# Mega2560.net
KiCad netlist of a schematic drawn in Altium Designer
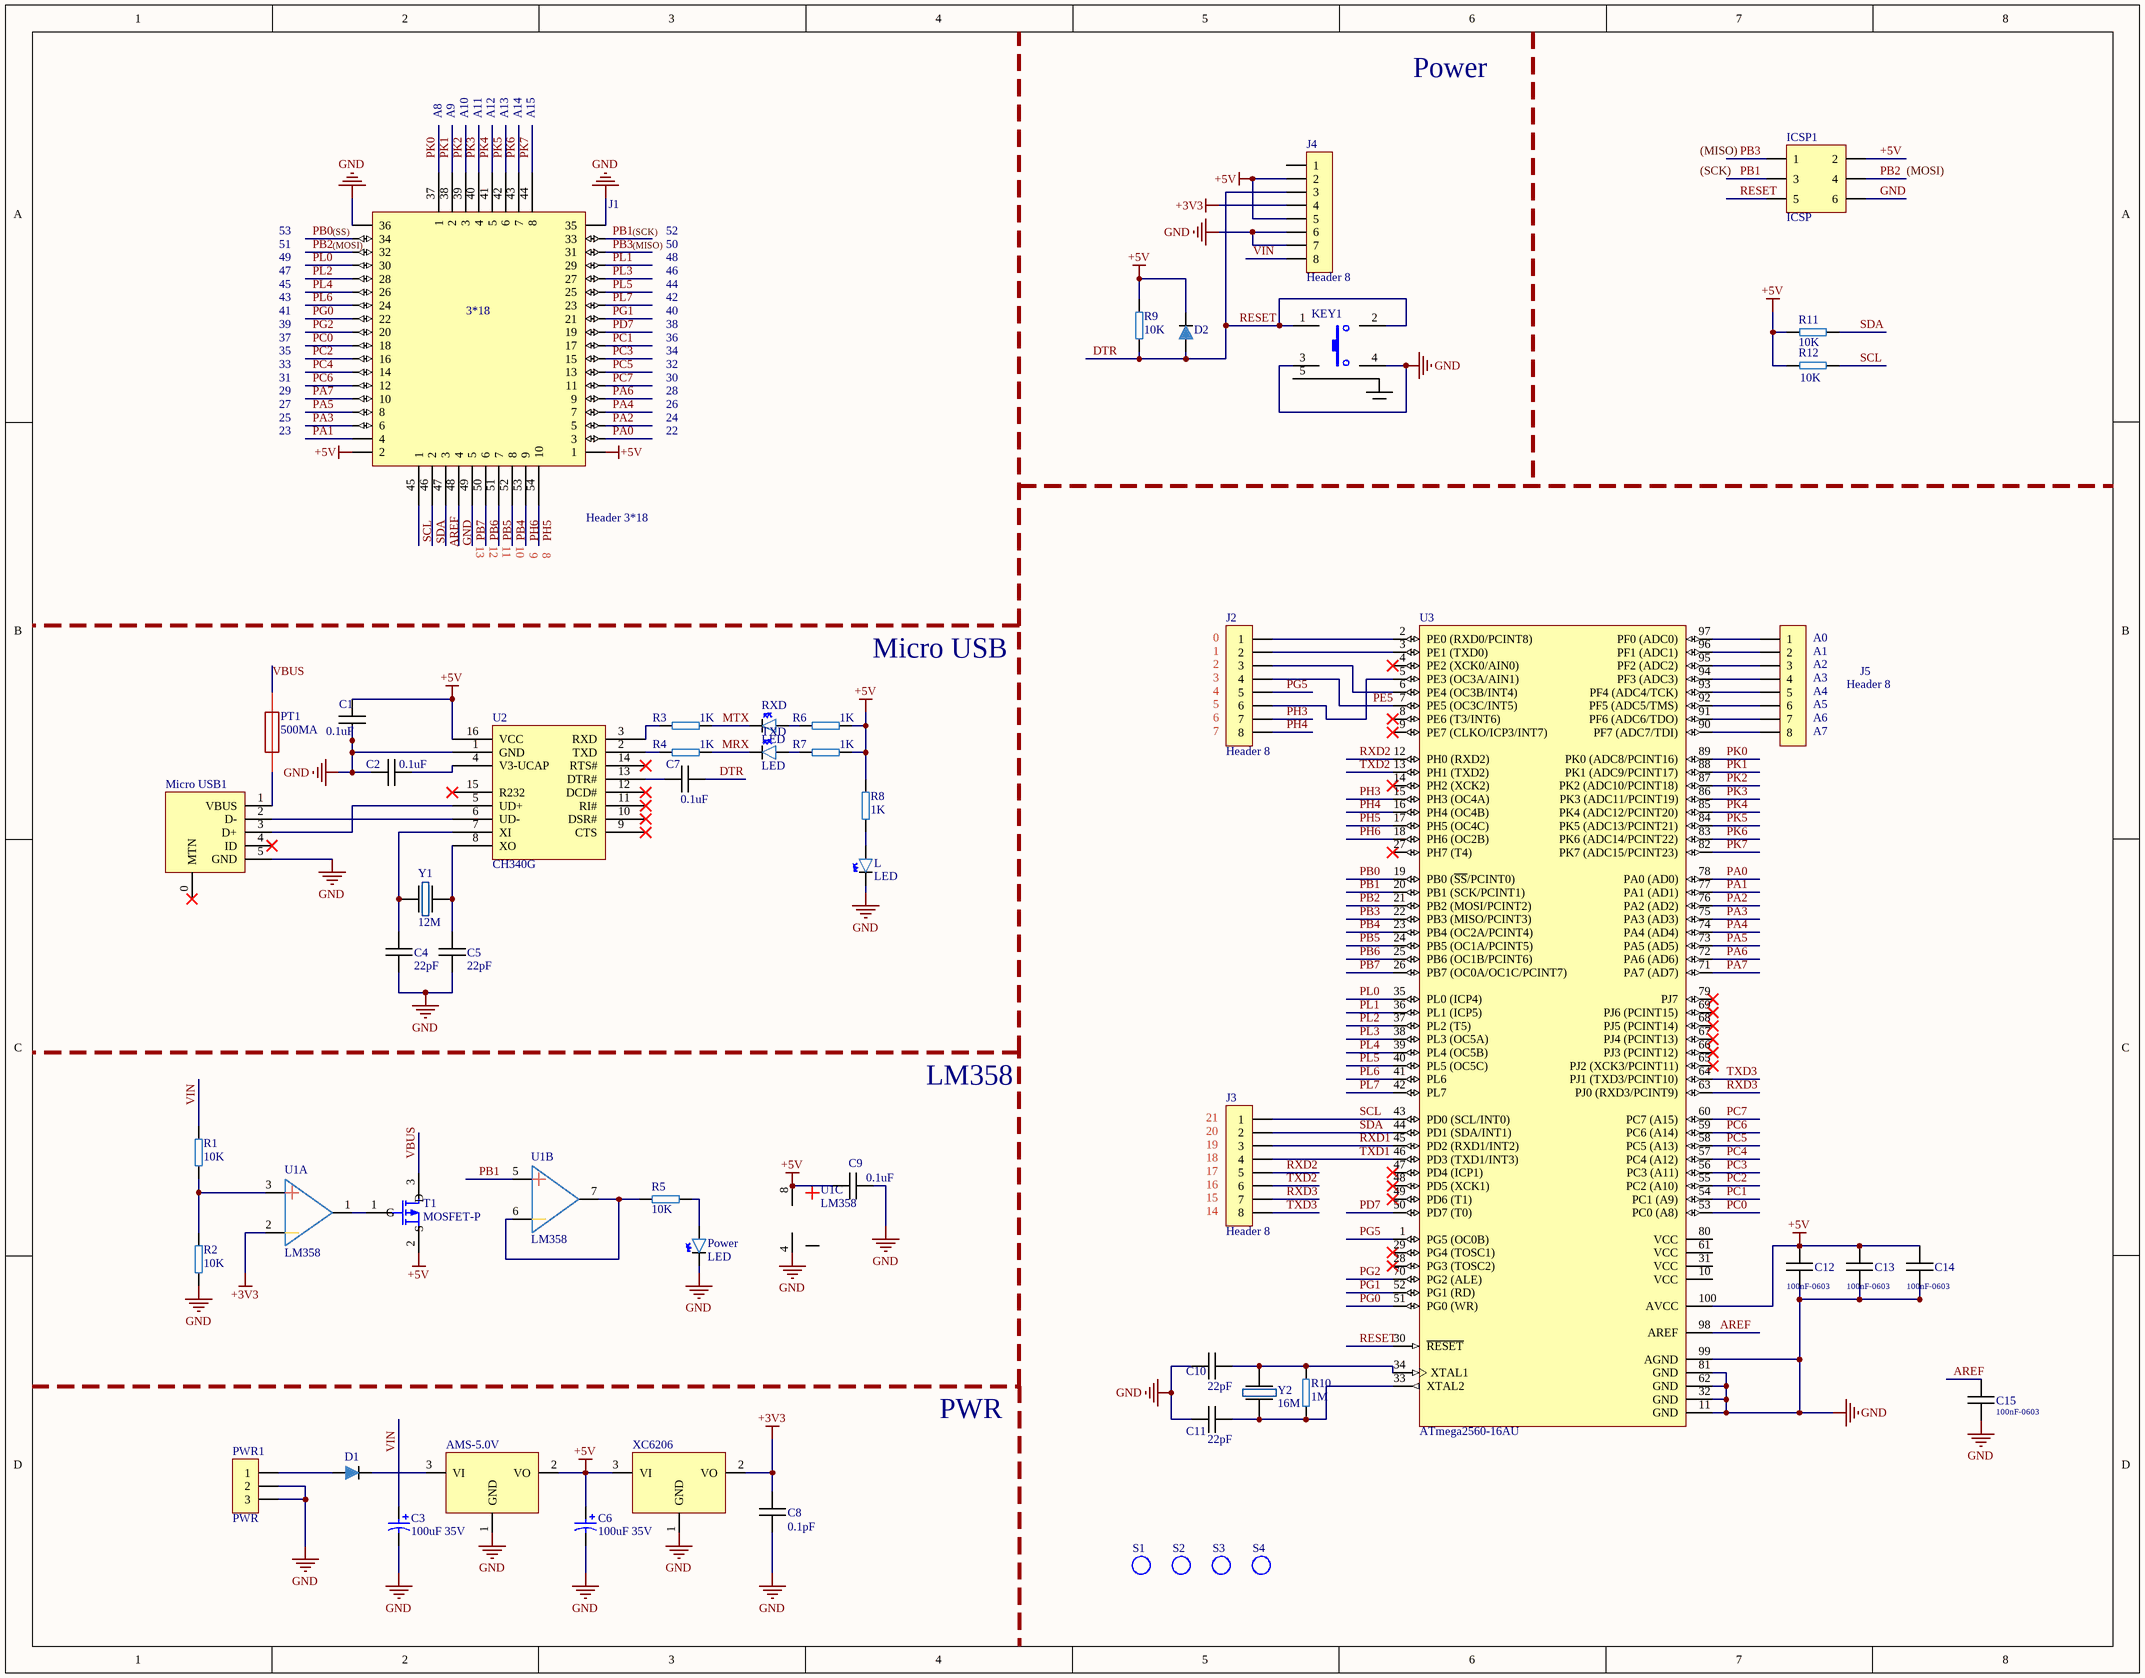
[diagram p0: Mega2560原理图.SchDoc]

(export (version "E")
  (design (tool "Eeschema 10.0.6"))
  (components
    (comp (ref "AMS-5.0V")
      (value "AMS1117-5.0")
      (footprint "AMS1117-5.0v")
      (libsource (lib "UNO原理图库") (part "AMS1117-5.0"))
    )
    (comp (ref "C1") (value "0.1uF") (footprint "0805") (libsource (lib "UNO原理图库") (part "CAP")))
    (comp (ref "C2") (value "0.1uF") (footprint "0805") (libsource (lib "UNO原理图库") (part "CAP")))
    (comp (ref "C3")
      (value "100uF 35V")
      (footprint "极性电容")
      (description "极性电容器")
      (fields (field (name "PUBLISHER") "Altium Limited"))
      (libsource (lib "UNO原理图库") (part "Cap Pol极性电容"))
    )
    (comp (ref "C4") (value "22pF") (footprint "0805") (libsource (lib "UNO原理图库") (part "CAP")))
    (comp (ref "C5") (value "22pF") (footprint "0805") (libsource (lib "UNO原理图库") (part "CAP")))
    (comp (ref "C6")
      (value "100uF 35V")
      (footprint "极性电容")
      (description "极性电容器")
      (fields (field (name "PUBLISHER") "Altium Limited"))
      (libsource (lib "UNO原理图库") (part "Cap Pol极性电容"))
    )
    (comp (ref "C7") (value "0.1uF") (footprint "0805") (libsource (lib "UNO原理图库") (part "CAP")))
    (comp (ref "C8") (value "0.1pF") (footprint "0805") (libsource (lib "UNO原理图库") (part "CAP电容")))
    (comp (ref "C9") (value "0.1uF") (footprint "0805") (libsource (lib "UNO原理图库") (part "CAP")))
    (comp (ref "C10") (value "22pF") (footprint "0805") (libsource (lib "UNO原理图库") (part "CAP")))
    (comp (ref "C11") (value "22pF") (footprint "0805") (libsource (lib "UNO原理图库") (part "CAP")))
    (comp (ref "C12")
      (value "100nF-0603")
      (footprint "0603_CAP")
      (description "0603 50V")
      (libsource (lib "Mega2560原理图库") (part "CAP-0603"))
    )
    (comp (ref "C13")
      (value "100nF-0603")
      (footprint "0603_CAP")
      (description "0603 50V")
      (libsource (lib "Mega2560原理图库") (part "CAP-0603"))
    )
    (comp (ref "C14")
      (value "100nF-0603")
      (footprint "0603_CAP")
      (description "0603 50V")
      (libsource (lib "Mega2560原理图库") (part "CAP-0603"))
    )
    (comp (ref "C15")
      (value "100nF-0603")
      (footprint "0603_CAP")
      (description "0603 50V")
      (libsource (lib "Mega2560原理图库") (part "CAP-0603"))
    )
    (comp (ref "D1") (value "二极管") (footprint "1206 正负") (libsource (lib "UNO原理图库") (part "二极管")))
    (comp (ref "D2") (value "二极管") (footprint "1206 正负") (libsource (lib "UNO原理图库") (part "二极管")))
    (comp (ref "ICSP1")
      (value "ICSP")
      (footprint "排针 2*3 PIN")
      (description "排针")
      (libsource (lib "Mega2560原理图库") (part "Header 2*3"))
    )
    (comp (ref "J1")
      (value "Header 3*18")
      (footprint "排针 3*18 PIN")
      (libsource (lib "Mega2560原理图库") (part "Header 3*18"))
    )
    (comp (ref "J2")
      (value "Header 8")
      (footprint "排针 8 PIN")
      (description "排针")
      (libsource (lib "") (part "Header 8_1"))
    )
    (comp (ref "J3")
      (value "Header 8")
      (footprint "排针 8 PIN")
      (description "排针")
      (libsource (lib "") (part "Header 8_1"))
    )
    (comp (ref "J4")
      (value "Header 8")
      (footprint "排针 8 PIN")
      (description "排针")
      (libsource (lib "Mega2560原理图库") (part "Header 8"))
    )
    (comp (ref "J5")
      (value "Header 8")
      (footprint "排针 8 PIN")
      (description "排针")
      (libsource (lib "Mega2560原理图库") (part "Header 8"))
    )
    (comp (ref "KEY1")
      (value "按键")
      (footprint "按键")
      (description "Switch")
      (fields (field (name "PUBLISHER") "Altium Limited"))
      (libsource (lib "Mega2560原理图库") (part "按键"))
    )
    (comp (ref "L") (value "LED") (footprint "0805 - LED") (libsource (lib "Mega2560原理图库") (part "LED")))
    (comp (ref "Micro USB1")
      (value "Micro USB")
      (footprint "MICRO-USB")
      (libsource (lib "UNO原理图库") (part "Micro USB"))
    )
    (comp (ref "Power") (value "LED") (footprint "0805 - LED") (libsource (lib "Mega2560原理图库") (part "LED")))
    (comp (ref "PT1")
      (value "500MA")
      (footprint "0805")
      (description "磁珠")
      (libsource (lib "UNO原理图库") (part "PT"))
    )
    (comp (ref "PWR1") (value "PWR") (footprint "DC电源") (libsource (lib "UNO原理图库") (part "PWR")))
    (comp (ref "R1") (value "10K") (footprint "0805") (libsource (lib "UNO原理图库") (part "RES")))
    (comp (ref "R2") (value "10K") (footprint "0805") (libsource (lib "UNO原理图库") (part "RES")))
    (comp (ref "R3") (value "1K") (footprint "0805") (libsource (lib "UNO原理图库") (part "RES")))
    (comp (ref "R4") (value "1K") (footprint "0805") (libsource (lib "UNO原理图库") (part "RES")))
    (comp (ref "R5") (value "10K") (footprint "0805") (libsource (lib "UNO原理图库") (part "RES")))
    (comp (ref "R6") (value "1K") (footprint "0805") (libsource (lib "UNO原理图库") (part "RES")))
    (comp (ref "R7") (value "1K") (footprint "0805") (libsource (lib "UNO原理图库") (part "RES")))
    (comp (ref "R8") (value "1K") (footprint "0805") (libsource (lib "UNO原理图库") (part "RES")))
    (comp (ref "R9") (value "10K") (footprint "0805") (libsource (lib "UNO原理图库") (part "RES")))
    (comp (ref "R10") (value "1M") (footprint "0805") (libsource (lib "UNO原理图库") (part "RES")))
    (comp (ref "R11") (value "10K") (footprint "0805") (libsource (lib "Mega2560原理图库") (part "电阻")))
    (comp (ref "R12") (value "10K") (footprint "0805") (libsource (lib "Mega2560原理图库") (part "电阻")))
    (comp (ref "RXD") (value "LED") (footprint "0805 - LED") (libsource (lib "Mega2560原理图库") (part "LED")))
    (comp (ref "S1") (value "散热孔") (footprint "散热孔") (libsource (lib "Mega2560原理图库") (part "散热孔")))
    (comp (ref "S2") (value "散热孔") (footprint "散热孔") (libsource (lib "Mega2560原理图库") (part "散热孔")))
    (comp (ref "S3") (value "散热孔") (footprint "散热孔") (libsource (lib "Mega2560原理图库") (part "散热孔")))
    (comp (ref "S4") (value "散热孔") (footprint "散热孔") (libsource (lib "Mega2560原理图库") (part "散热孔")))
    (comp (ref "T1")
      (value "MOSFET-P")
      (footprint "SI2301")
      (description "摩斯管")
      (fields (field (name "PUBLISHER") "Altium Limited"))
      (libsource (lib "Mega2560原理图库") (part "MOSFET-P(MOS)"))
    )
    (comp (ref "TXD") (value "LED") (footprint "0805 - LED") (libsource (lib "Mega2560原理图库") (part "LED")))
    (comp (ref "U1")
      (value "LM358")
      (footprint "LM358")
      (description "电源控制")
      (libsource (lib "UNO原理图库") (part "LM358"))
    )
    (comp (ref "U2") (value "CH340G") (footprint "CH340G") (libsource (lib "UNO原理图库") (part "CH340G")))
    (comp (ref "U3")
      (value "ATmega2560-16AU")
      (footprint "ATMEGA2560-AU")
      (libsource (lib "Mega2560原理图库") (part "ATmega2560-16AU"))
    )
    (comp (ref "XC6206")
      (value "XC6206P332")
      (footprint "XC6206P332-3.3v")
      (libsource (lib "UNO原理图库") (part "XC6206P332"))
    )
    (comp (ref "Y1") (value "12M") (footprint "贴片晶振") (libsource (lib "UNO原理图库") (part "CRYSTAL")))
    (comp (ref "Y2") (value "16M") (footprint "贴片晶振") (libsource (lib "UNO原理图库") (part "CRYSTAL")))
  )
  (nets
    (net (code "1") (name "+3V3") (class "Default")
      (node (ref "C8") (pin "2") (pinfunction "2_2") (pintype "passive"))
      (node (ref "J4") (pin "4") (pinfunction "4_4") (pintype "passive"))
      (node (ref "U1") (pin "2") (pinfunction "2_2") (pintype "passive"))
      (node (ref "XC6206") (pin "2") (pinfunction "VO_2") (pintype "passive"))
    )
    (net (code "2") (name "+5V") (class "Default")
      (node (ref "AMS-5.0V") (pin "2") (pinfunction "VO_2") (pintype "passive"))
      (node (ref "C1") (pin "2") (pinfunction "2_2") (pintype "passive"))
      (node (ref "C12") (pin "2") (pinfunction "2_2") (pintype "passive"))
      (node (ref "C13") (pin "2") (pinfunction "2_2") (pintype "passive"))
      (node (ref "C14") (pin "2") (pinfunction "2_2") (pintype "passive"))
      (node (ref "C6") (pin "1") (pinfunction "1_1") (pintype "passive"))
      (node (ref "C9") (pin "1") (pinfunction "1_1") (pintype "passive"))
      (node (ref "D2") (pin "2") (pinfunction "2_2") (pintype "passive"))
      (node (ref "ICSP1") (pin "2") (pinfunction "2_2") (pintype "passive"))
      (node (ref "J1") (pin "1") (pinfunction "1_1") (pintype "power_in"))
      (node (ref "J1") (pin "2") (pinfunction "2_2") (pintype "power_in"))
      (node (ref "J4") (pin "2") (pinfunction "2_2") (pintype "passive"))
      (node (ref "J4") (pin "5") (pinfunction "5_5") (pintype "passive"))
      (node (ref "R11") (pin "2") (pinfunction "2_2") (pintype "passive"))
      (node (ref "R12") (pin "2") (pinfunction "2_2") (pintype "passive"))
      (node (ref "R6") (pin "2") (pinfunction "2_2") (pintype "passive"))
      (node (ref "R7") (pin "2") (pinfunction "2_2") (pintype "passive"))
      (node (ref "R8") (pin "2") (pinfunction "2_2") (pintype "passive"))
      (node (ref "R9") (pin "2") (pinfunction "2_2") (pintype "passive"))
      (node (ref "T1") (pin "2") (pinfunction "S_2") (pintype "passive"))
      (node (ref "U1") (pin "8") (pinfunction "8_8") (pintype "passive"))
      (node (ref "U2") (pin "16") (pinfunction "VCC_16") (pintype "passive"))
      (node (ref "U3") (pin "100") (pinfunction "AVCC_100") (pintype "power_in"))
      (node (ref "XC6206") (pin "3") (pinfunction "VI_3") (pintype "passive"))
    )
    (net (code "3") (name "/AREF") (class "Default")
      (node (ref "C15") (pin "2") (pinfunction "2_2") (pintype "passive"))
      (node (ref "J1") (pin "47") (pinfunction "3_47") (pintype "passive"))
      (node (ref "U3") (pin "98") (pinfunction "AREF_98") (pintype "power_in"))
    )
    (net (code "4") (name "/DTR") (class "Default")
      (node (ref "C7") (pin "1") (pinfunction "1_1") (pintype "passive"))
      (node (ref "D2") (pin "1") (pinfunction "1_1") (pintype "passive"))
      (node (ref "ICSP1") (pin "5") (pinfunction "5_5") (pintype "passive"))
      (node (ref "J4") (pin "3") (pinfunction "3_3") (pintype "passive"))
      (node (ref "KEY1") (pin "1") (pinfunction "1_1") (pintype "passive"))
      (node (ref "KEY1") (pin "2") (pinfunction "2_2") (pintype "passive"))
      (node (ref "R9") (pin "1") (pinfunction "1_1") (pintype "passive"))
      (node (ref "U3") (pin "30") (pinfunction "~{RESET}_30") (pintype "input"))
    )
    (net (code "5") (name "/MRX") (class "Default")
      (node (ref "R4") (pin "2") (pinfunction "2_2") (pintype "passive"))
      (node (ref "TXD") (pin "2") (pinfunction "2_2") (pintype "passive"))
    )
    (net (code "6") (name "/MTX") (class "Default")
      (node (ref "R3") (pin "2") (pinfunction "2_2") (pintype "passive"))
      (node (ref "RXD") (pin "2") (pinfunction "2_2") (pintype "passive"))
    )
    (net (code "7") (name "/PA0") (class "Default")
      (node (ref "J1") (pin "3") (pinfunction "3_3") (pintype "bidirectional"))
      (node (ref "U3") (pin "78") (pinfunction "PA0_(AD0)_78") (pintype "bidirectional"))
    )
    (net (code "8") (name "/PA1") (class "Default")
      (node (ref "J1") (pin "4") (pinfunction "4_4") (pintype "passive"))
      (node (ref "U3") (pin "77") (pinfunction "PA1_(AD1)_77") (pintype "bidirectional"))
    )
    (net (code "9") (name "/PA2") (class "Default")
      (node (ref "J1") (pin "5") (pinfunction "5_5") (pintype "bidirectional"))
      (node (ref "U3") (pin "76") (pinfunction "PA2_(AD2)_76") (pintype "bidirectional"))
    )
    (net (code "10") (name "/PA3") (class "Default")
      (node (ref "J1") (pin "6") (pinfunction "6_6") (pintype "bidirectional"))
      (node (ref "U3") (pin "75") (pinfunction "PA3_(AD3)_75") (pintype "bidirectional"))
    )
    (net (code "11") (name "/PA4") (class "Default")
      (node (ref "J1") (pin "7") (pinfunction "7_7") (pintype "bidirectional"))
      (node (ref "U3") (pin "74") (pinfunction "PA4_(AD4)_74") (pintype "bidirectional"))
    )
    (net (code "12") (name "/PA5") (class "Default")
      (node (ref "J1") (pin "8") (pinfunction "8_8") (pintype "bidirectional"))
      (node (ref "U3") (pin "73") (pinfunction "PA5_(AD5)_73") (pintype "bidirectional"))
    )
    (net (code "13") (name "/PA6") (class "Default")
      (node (ref "J1") (pin "9") (pinfunction "9_9") (pintype "bidirectional"))
      (node (ref "U3") (pin "72") (pinfunction "PA6_(AD6)_72") (pintype "bidirectional"))
    )
    (net (code "14") (name "/PA7") (class "Default")
      (node (ref "J1") (pin "10") (pinfunction "10_10") (pintype "bidirectional"))
      (node (ref "U3") (pin "71") (pinfunction "PA7_(AD7)_71") (pintype "bidirectional"))
    )
    (net (code "15") (name "/PB0") (class "Default")
      (node (ref "J1") (pin "34") (pinfunction "34_34") (pintype "bidirectional"))
      (node (ref "U3") (pin "19") (pinfunction "PB0_(~{SS}/PCINT0)_19") (pintype "bidirectional"))
    )
    (net (code "16") (name "/PB1") (class "Default")
      (node (ref "ICSP1") (pin "3") (pinfunction "3_3") (pintype "passive"))
      (node (ref "J1") (pin "33") (pinfunction "33_33") (pintype "bidirectional"))
      (node (ref "U1") (pin "5") (pinfunction "5_5") (pintype "passive"))
      (node (ref "U3") (pin "20") (pinfunction "PB1_(SCK/PCINT1)_20") (pintype "bidirectional"))
    )
    (net (code "17") (name "/PB2") (class "Default")
      (node (ref "ICSP1") (pin "4") (pinfunction "4_4") (pintype "passive"))
      (node (ref "J1") (pin "32") (pinfunction "32_32") (pintype "bidirectional"))
      (node (ref "U3") (pin "21") (pinfunction "PB2_(MOSI/PCINT2)_21") (pintype "bidirectional"))
    )
    (net (code "18") (name "/PB3") (class "Default")
      (node (ref "ICSP1") (pin "1") (pinfunction "1_1") (pintype "passive"))
      (node (ref "J1") (pin "31") (pinfunction "31_31") (pintype "bidirectional"))
      (node (ref "U3") (pin "22") (pinfunction "PB3_(MISO/PCINT3)_22") (pintype "bidirectional"))
    )
    (net (code "19") (name "/PB4") (class "Default")
      (node (ref "J1") (pin "52") (pinfunction "8_52") (pintype "passive"))
      (node (ref "U3") (pin "23") (pinfunction "PB4_(OC2A/PCINT4)_23") (pintype "bidirectional"))
    )
    (net (code "20") (name "/PB5") (class "Default")
      (node (ref "J1") (pin "51") (pinfunction "7_51") (pintype "passive"))
      (node (ref "U3") (pin "24") (pinfunction "PB5_(OC1A/PCINT5)_24") (pintype "bidirectional"))
    )
    (net (code "21") (name "/PB6") (class "Default")
      (node (ref "J1") (pin "50") (pinfunction "6_50") (pintype "passive"))
      (node (ref "U3") (pin "25") (pinfunction "PB6_(OC1B/PCINT6)_25") (pintype "bidirectional"))
    )
    (net (code "22") (name "/PB7") (class "Default")
      (node (ref "J1") (pin "49") (pinfunction "5_49") (pintype "passive"))
      (node (ref "U3") (pin "26") (pinfunction "PB7_(OC0A/OC1C/PCINT7)_26") (pintype "bidirectional"))
    )
    (net (code "23") (name "/PC0") (class "Default")
      (node (ref "J1") (pin "18") (pinfunction "18_18") (pintype "bidirectional"))
      (node (ref "U3") (pin "53") (pinfunction "PC0_(A8)_53") (pintype "bidirectional"))
    )
    (net (code "24") (name "/PC1") (class "Default")
      (node (ref "J1") (pin "17") (pinfunction "17_17") (pintype "bidirectional"))
      (node (ref "U3") (pin "54") (pinfunction "PC1_(A9)_54") (pintype "bidirectional"))
    )
    (net (code "25") (name "/PC2") (class "Default")
      (node (ref "J1") (pin "16") (pinfunction "16_16") (pintype "bidirectional"))
      (node (ref "U3") (pin "55") (pinfunction "PC2_(A10)_55") (pintype "bidirectional"))
    )
    (net (code "26") (name "/PC3") (class "Default")
      (node (ref "J1") (pin "15") (pinfunction "15_15") (pintype "bidirectional"))
      (node (ref "U3") (pin "56") (pinfunction "PC3_(A11)_56") (pintype "bidirectional"))
    )
    (net (code "27") (name "/PC4") (class "Default")
      (node (ref "J1") (pin "14") (pinfunction "14_14") (pintype "bidirectional"))
      (node (ref "U3") (pin "57") (pinfunction "PC4_(A12)_57") (pintype "bidirectional"))
    )
    (net (code "28") (name "/PC5") (class "Default")
      (node (ref "J1") (pin "13") (pinfunction "13_13") (pintype "bidirectional"))
      (node (ref "U3") (pin "58") (pinfunction "PC5_(A13)_58") (pintype "bidirectional"))
    )
    (net (code "29") (name "/PC6") (class "Default")
      (node (ref "J1") (pin "12") (pinfunction "12_12") (pintype "bidirectional"))
      (node (ref "U3") (pin "59") (pinfunction "PC6_(A14)_59") (pintype "bidirectional"))
    )
    (net (code "30") (name "/PC7") (class "Default")
      (node (ref "J1") (pin "11") (pinfunction "11_11") (pintype "bidirectional"))
      (node (ref "U3") (pin "60") (pinfunction "PC7_(A15)_60") (pintype "bidirectional"))
    )
    (net (code "31") (name "/PD7") (class "Default")
      (node (ref "J1") (pin "19") (pinfunction "19_19") (pintype "bidirectional"))
      (node (ref "U3") (pin "50") (pinfunction "PD7_(T0)_50") (pintype "bidirectional"))
    )
    (net (code "32") (name "/PE5") (class "Default")
      (node (ref "J2") (pin "4") (pinfunction "4_4") (pintype "passive"))
      (node (ref "U3") (pin "7") (pinfunction "PE5_(OC3C/INT5)_7") (pintype "bidirectional"))
    )
    (net (code "33") (name "/PG0") (class "Default")
      (node (ref "J1") (pin "22") (pinfunction "22_22") (pintype "bidirectional"))
      (node (ref "U3") (pin "51") (pinfunction "PG0_(WR)_51") (pintype "bidirectional"))
    )
    (net (code "34") (name "/PG1") (class "Default")
      (node (ref "J1") (pin "21") (pinfunction "21_21") (pintype "bidirectional"))
      (node (ref "U3") (pin "52") (pinfunction "PG1_(RD)_52") (pintype "bidirectional"))
    )
    (net (code "35") (name "/PG2") (class "Default")
      (node (ref "J1") (pin "20") (pinfunction "20_20") (pintype "bidirectional"))
      (node (ref "U3") (pin "70") (pinfunction "PG2_(ALE)_70") (pintype "bidirectional"))
    )
    (net (code "36") (name "/PG5") (class "Default")
      (node (ref "J2") (pin "5") (pinfunction "5_5") (pintype "passive"))
      (node (ref "U3") (pin "1") (pinfunction "PG5_(OC0B)_1") (pintype "bidirectional"))
    )
    (net (code "37") (name "/PH3") (class "Default")
      (node (ref "J2") (pin "7") (pinfunction "7_7") (pintype "passive"))
      (node (ref "U3") (pin "15") (pinfunction "PH3_(OC4A)_15") (pintype "bidirectional"))
    )
    (net (code "38") (name "/PH4") (class "Default")
      (node (ref "J2") (pin "8") (pinfunction "8_8") (pintype "passive"))
      (node (ref "U3") (pin "16") (pinfunction "PH4_(OC4B)_16") (pintype "bidirectional"))
    )
    (net (code "39") (name "/PH5") (class "Default")
      (node (ref "J1") (pin "54") (pinfunction "10_54") (pintype "passive"))
      (node (ref "U3") (pin "17") (pinfunction "PH5_(OC4C)_17") (pintype "bidirectional"))
    )
    (net (code "40") (name "/PH6") (class "Default")
      (node (ref "J1") (pin "53") (pinfunction "9_53") (pintype "passive"))
      (node (ref "U3") (pin "18") (pinfunction "PH6_(OC2B)_18") (pintype "bidirectional"))
    )
    (net (code "41") (name "/PK0") (class "Default")
      (node (ref "J1") (pin "37") (pinfunction "1_37") (pintype "passive"))
      (node (ref "U3") (pin "89") (pinfunction "PK0_(ADC8/PCINT16)_89") (pintype "bidirectional"))
    )
    (net (code "42") (name "/PK1") (class "Default")
      (node (ref "J1") (pin "38") (pinfunction "2_38") (pintype "passive"))
      (node (ref "U3") (pin "88") (pinfunction "PK1_(ADC9/PCINT17)_88") (pintype "bidirectional"))
    )
    (net (code "43") (name "/PK2") (class "Default")
      (node (ref "J1") (pin "39") (pinfunction "3_39") (pintype "passive"))
      (node (ref "U3") (pin "87") (pinfunction "PK2_(ADC10/PCINT18)_87") (pintype "bidirectional"))
    )
    (net (code "44") (name "/PK3") (class "Default")
      (node (ref "J1") (pin "40") (pinfunction "4_40") (pintype "passive"))
      (node (ref "U3") (pin "86") (pinfunction "PK3_(ADC11/PCINT19)_86") (pintype "bidirectional"))
    )
    (net (code "45") (name "/PK4") (class "Default")
      (node (ref "J1") (pin "41") (pinfunction "5_41") (pintype "passive"))
      (node (ref "U3") (pin "85") (pinfunction "PK4_(ADC12/PCINT20)_85") (pintype "bidirectional"))
    )
    (net (code "46") (name "/PK5") (class "Default")
      (node (ref "J1") (pin "42") (pinfunction "6_42") (pintype "passive"))
      (node (ref "U3") (pin "84") (pinfunction "PK5_(ADC13/PCINT21)_84") (pintype "bidirectional"))
    )
    (net (code "47") (name "/PK6") (class "Default")
      (node (ref "J1") (pin "43") (pinfunction "7_43") (pintype "passive"))
      (node (ref "U3") (pin "83") (pinfunction "PK6_(ADC14/PCINT22)_83") (pintype "bidirectional"))
    )
    (net (code "48") (name "/PK7") (class "Default")
      (node (ref "J1") (pin "44") (pinfunction "8_44") (pintype "passive"))
      (node (ref "U3") (pin "82") (pinfunction "PK7_(ADC15/PCINT23)_82") (pintype "bidirectional"))
    )
    (net (code "49") (name "/PL0") (class "Default")
      (node (ref "J1") (pin "30") (pinfunction "30_30") (pintype "bidirectional"))
      (node (ref "U3") (pin "35") (pinfunction "PL0_(ICP4)_35") (pintype "bidirectional"))
    )
    (net (code "50") (name "/PL1") (class "Default")
      (node (ref "J1") (pin "29") (pinfunction "29_29") (pintype "bidirectional"))
      (node (ref "U3") (pin "36") (pinfunction "PL1_(ICP5)_36") (pintype "bidirectional"))
    )
    (net (code "51") (name "/PL2") (class "Default")
      (node (ref "J1") (pin "28") (pinfunction "28_28") (pintype "bidirectional"))
      (node (ref "U3") (pin "37") (pinfunction "PL2_(T5)_37") (pintype "bidirectional"))
    )
    (net (code "52") (name "/PL3") (class "Default")
      (node (ref "J1") (pin "27") (pinfunction "27_27") (pintype "bidirectional"))
      (node (ref "U3") (pin "38") (pinfunction "PL3_(OC5A)_38") (pintype "bidirectional"))
    )
    (net (code "53") (name "/PL4") (class "Default")
      (node (ref "J1") (pin "26") (pinfunction "26_26") (pintype "bidirectional"))
      (node (ref "U3") (pin "39") (pinfunction "PL4_(OC5B)_39") (pintype "bidirectional"))
    )
    (net (code "54") (name "/PL5") (class "Default")
      (node (ref "J1") (pin "25") (pinfunction "25_25") (pintype "bidirectional"))
      (node (ref "U3") (pin "40") (pinfunction "PL5_(OC5C)_40") (pintype "bidirectional"))
    )
    (net (code "55") (name "/PL6") (class "Default")
      (node (ref "J1") (pin "24") (pinfunction "24_24") (pintype "bidirectional"))
      (node (ref "U3") (pin "41") (pinfunction "PL6_41") (pintype "bidirectional"))
    )
    (net (code "56") (name "/PL7") (class "Default")
      (node (ref "J1") (pin "23") (pinfunction "23_23") (pintype "bidirectional"))
      (node (ref "U3") (pin "42") (pinfunction "PL7_42") (pintype "bidirectional"))
    )
    (net (code "57") (name "/RXD1") (class "Default")
      (node (ref "J3") (pin "3") (pinfunction "3_3") (pintype "passive"))
      (node (ref "U3") (pin "45") (pinfunction "PD2_(RXD1/INT2)_45") (pintype "bidirectional"))
    )
    (net (code "58") (name "/RXD2") (class "Default")
      (node (ref "J3") (pin "5") (pinfunction "5_5") (pintype "passive"))
      (node (ref "U3") (pin "12") (pinfunction "PH0_(RXD2)_12") (pintype "bidirectional"))
    )
    (net (code "59") (name "/RXD3") (class "Default")
      (node (ref "J3") (pin "7") (pinfunction "7_7") (pintype "passive"))
      (node (ref "U3") (pin "63") (pinfunction "PJ0_(RXD3/PCINT9)_63") (pintype "bidirectional"))
    )
    (net (code "60") (name "/SCL") (class "Default")
      (node (ref "J1") (pin "45") (pinfunction "1_45") (pintype "passive"))
      (node (ref "J3") (pin "1") (pinfunction "1_1") (pintype "passive"))
      (node (ref "R12") (pin "1") (pinfunction "1_1") (pintype "passive"))
      (node (ref "U3") (pin "43") (pinfunction "PD0_(SCL/INT0)_43") (pintype "bidirectional"))
    )
    (net (code "61") (name "/SDA") (class "Default")
      (node (ref "J1") (pin "46") (pinfunction "2_46") (pintype "passive"))
      (node (ref "J3") (pin "2") (pinfunction "2_2") (pintype "passive"))
      (node (ref "R11") (pin "1") (pinfunction "1_1") (pintype "passive"))
      (node (ref "U3") (pin "44") (pinfunction "PD1_(SDA/INT1)_44") (pintype "bidirectional"))
    )
    (net (code "62") (name "/TXD1") (class "Default")
      (node (ref "J3") (pin "4") (pinfunction "4_4") (pintype "passive"))
      (node (ref "U3") (pin "46") (pinfunction "PD3_(TXD1/INT3)_46") (pintype "bidirectional"))
    )
    (net (code "63") (name "/TXD2") (class "Default")
      (node (ref "J3") (pin "6") (pinfunction "6_6") (pintype "passive"))
      (node (ref "U3") (pin "13") (pinfunction "PH1_(TXD2)_13") (pintype "bidirectional"))
    )
    (net (code "64") (name "/TXD3") (class "Default")
      (node (ref "J3") (pin "8") (pinfunction "8_8") (pintype "passive"))
      (node (ref "U3") (pin "64") (pinfunction "PJ1_(TXD3/PCINT10)_64") (pintype "bidirectional"))
    )
    (net (code "65") (name "/VBUS") (class "Default")
      (node (ref "PT1") (pin "2") (pinfunction "2_2") (pintype "passive"))
      (node (ref "T1") (pin "3") (pinfunction "D_3") (pintype "passive"))
    )
    (net (code "66") (name "/VIN") (class "Default")
      (node (ref "C3") (pin "1") (pinfunction "1_1") (pintype "passive"))
      (node (ref "J4") (pin "8") (pinfunction "8_8") (pintype "passive"))
      (node (ref "R1") (pin "2") (pinfunction "2_2") (pintype "passive"))
    )
    (net (code "67") (name "GND") (class "Default")
      (node (ref "AMS-5.0V") (pin "1") (pinfunction "GND_1") (pintype "passive"))
      (node (ref "C1") (pin "1") (pinfunction "1_1") (pintype "passive"))
      (node (ref "C10") (pin "2") (pinfunction "2_2") (pintype "passive"))
      (node (ref "C11") (pin "2") (pinfunction "2_2") (pintype "passive"))
      (node (ref "C12") (pin "1") (pinfunction "1_1") (pintype "passive"))
      (node (ref "C13") (pin "1") (pinfunction "1_1") (pintype "passive"))
      (node (ref "C14") (pin "1") (pinfunction "1_1") (pintype "passive"))
      (node (ref "C15") (pin "1") (pinfunction "1_1") (pintype "passive"))
      (node (ref "C2") (pin "1") (pinfunction "1_1") (pintype "passive"))
      (node (ref "C3") (pin "2") (pinfunction "2_2") (pintype "passive"))
      (node (ref "C4") (pin "1") (pinfunction "1_1") (pintype "passive"))
      (node (ref "C5") (pin "1") (pinfunction "1_1") (pintype "passive"))
      (node (ref "C6") (pin "2") (pinfunction "2_2") (pintype "passive"))
      (node (ref "C8") (pin "1") (pinfunction "1_1") (pintype "passive"))
      (node (ref "C9") (pin "2") (pinfunction "2_2") (pintype "passive"))
      (node (ref "ICSP1") (pin "6") (pinfunction "6_6") (pintype "passive"))
      (node (ref "J1") (pin "35") (pinfunction "35_35") (pintype "power_in"))
      (node (ref "J1") (pin "36") (pinfunction "36_36") (pintype "power_in"))
      (node (ref "J1") (pin "48") (pinfunction "4_48") (pintype "passive"))
      (node (ref "J4") (pin "6") (pinfunction "6_6") (pintype "passive"))
      (node (ref "J4") (pin "7") (pinfunction "7_7") (pintype "passive"))
      (node (ref "KEY1") (pin "3") (pinfunction "3_3") (pintype "passive"))
      (node (ref "KEY1") (pin "4") (pinfunction "4_4") (pintype "passive"))
      (node (ref "L") (pin "2") (pinfunction "2_2") (pintype "passive"))
      (node (ref "Micro USB1") (pin "5") (pinfunction "GND_5") (pintype "passive"))
      (node (ref "PWR1") (pin "2") (pinfunction "2_2") (pintype "passive"))
      (node (ref "PWR1") (pin "3") (pinfunction "3_3") (pintype "passive"))
      (node (ref "Power") (pin "2") (pinfunction "2_2") (pintype "passive"))
      (node (ref "R2") (pin "1") (pinfunction "1_1") (pintype "passive"))
      (node (ref "U1") (pin "4") (pinfunction "4_4") (pintype "passive"))
      (node (ref "U2") (pin "1") (pinfunction "GND_1") (pintype "passive"))
      (node (ref "U3") (pin "11") (pinfunction "GND_11") (pintype "power_in"))
      (node (ref "U3") (pin "32") (pinfunction "GND_32") (pintype "power_in"))
      (node (ref "U3") (pin "62") (pinfunction "GND_62") (pintype "power_in"))
      (node (ref "U3") (pin "81") (pinfunction "GND_81") (pintype "power_in"))
      (node (ref "U3") (pin "99") (pinfunction "AGND_99") (pintype "power_in"))
      (node (ref "XC6206") (pin "1") (pinfunction "GND_1") (pintype "passive"))
    )
    (net (code "68") (name "Net-(AMS-5.0V-VI)") (class "Default")
      (node (ref "AMS-5.0V") (pin "3") (pinfunction "VI_3") (pintype "passive"))
      (node (ref "D1") (pin "2") (pinfunction "2_2") (pintype "passive"))
    )
    (net (code "69") (name "Net-(D1-Pad1)") (class "Default")
      (node (ref "D1") (pin "1") (pinfunction "1_1") (pintype "passive"))
      (node (ref "PWR1") (pin "1") (pinfunction "1_1") (pintype "passive"))
    )
    (net (code "70") (name "Net-(L-Pad1)") (class "Default")
      (node (ref "L") (pin "1") (pinfunction "1_1") (pintype "passive"))
      (node (ref "R8") (pin "1") (pinfunction "1_1") (pintype "passive"))
    )
    (net (code "71") (name "Net-(Micro USB1-D+)") (class "Default")
      (node (ref "Micro USB1") (pin "3") (pinfunction "D+_3") (pintype "passive"))
      (node (ref "U2") (pin "5") (pinfunction "UD+_5") (pintype "passive"))
    )
    (net (code "72") (name "Net-(Micro USB1-D-)") (class "Default")
      (node (ref "Micro USB1") (pin "2") (pinfunction "D-_2") (pintype "passive"))
      (node (ref "U2") (pin "6") (pinfunction "UD-_6") (pintype "passive"))
    )
    (net (code "73") (name "Net-(Micro USB1-VBUS)") (class "Default")
      (node (ref "Micro USB1") (pin "1") (pinfunction "VBUS_1") (pintype "passive"))
      (node (ref "PT1") (pin "1") (pinfunction "1_1") (pintype "passive"))
    )
    (net (code "74") (name "Net-(Power-Pad1)") (class "Default")
      (node (ref "Power") (pin "1") (pinfunction "1_1") (pintype "passive"))
      (node (ref "R5") (pin "2") (pinfunction "2_2") (pintype "passive"))
    )
    (net (code "75") (name "Net-(R1-Pad1)") (class "Default")
      (node (ref "R1") (pin "1") (pinfunction "1_1") (pintype "passive"))
      (node (ref "R2") (pin "2") (pinfunction "2_2") (pintype "passive"))
      (node (ref "U1") (pin "3") (pinfunction "3_3") (pintype "passive"))
    )
    (net (code "76") (name "Net-(R5-Pad1)") (class "Default")
      (node (ref "R5") (pin "1") (pinfunction "1_1") (pintype "passive"))
      (node (ref "U1") (pin "6") (pinfunction "6_6") (pintype "passive"))
      (node (ref "U1") (pin "7") (pinfunction "7_7") (pintype "passive"))
    )
    (net (code "77") (name "Net-(R6-Pad1)") (class "Default")
      (node (ref "R6") (pin "1") (pinfunction "1_1") (pintype "passive"))
      (node (ref "RXD") (pin "1") (pinfunction "1_1") (pintype "passive"))
    )
    (net (code "78") (name "Net-(R7-Pad1)") (class "Default")
      (node (ref "R7") (pin "1") (pinfunction "1_1") (pintype "passive"))
      (node (ref "TXD") (pin "1") (pinfunction "1_1") (pintype "passive"))
    )
    (net (code "79") (name "Net-(T1-G)") (class "Default")
      (node (ref "T1") (pin "1") (pinfunction "G_1") (pintype "passive"))
      (node (ref "U1") (pin "1") (pinfunction "1_1") (pintype "passive"))
    )
    (net (code "80") (name "Net-(U2-DTR#)") (class "Default")
      (node (ref "C7") (pin "2") (pinfunction "2_2") (pintype "passive"))
      (node (ref "U2") (pin "13") (pinfunction "DTR#_13") (pintype "passive"))
    )
    (net (code "81") (name "Net-(U2-RXD)") (class "Default")
      (node (ref "R3") (pin "1") (pinfunction "1_1") (pintype "passive"))
      (node (ref "U2") (pin "3") (pinfunction "RXD_3") (pintype "passive"))
    )
    (net (code "82") (name "Net-(U2-TXD)") (class "Default")
      (node (ref "R4") (pin "1") (pinfunction "1_1") (pintype "passive"))
      (node (ref "U2") (pin "2") (pinfunction "TXD_2") (pintype "passive"))
    )
    (net (code "83") (name "Net-(U2-V3-UCAP)") (class "Default")
      (node (ref "C2") (pin "2") (pinfunction "2_2") (pintype "passive"))
      (node (ref "U2") (pin "4") (pinfunction "V3-UCAP_4") (pintype "passive"))
    )
    (net (code "84") (name "Net-(U2-XI)") (class "Default")
      (node (ref "C4") (pin "2") (pinfunction "2_2") (pintype "passive"))
      (node (ref "U2") (pin "7") (pinfunction "XI_7") (pintype "passive"))
      (node (ref "Y1") (pin "1") (pinfunction "1_1") (pintype "passive"))
    )
    (net (code "85") (name "Net-(U2-XO)") (class "Default")
      (node (ref "C5") (pin "2") (pinfunction "2_2") (pintype "passive"))
      (node (ref "U2") (pin "8") (pinfunction "XO_8") (pintype "passive"))
      (node (ref "Y1") (pin "2") (pinfunction "2_2") (pintype "passive"))
    )
    (net (code "86") (name "Net-(U3-PE0_(RXD0{slash}PCINT8))") (class "Default")
      (node (ref "J2") (pin "1") (pinfunction "1_1") (pintype "passive"))
      (node (ref "U3") (pin "2") (pinfunction "PE0_(RXD0/PCINT8)_2") (pintype "bidirectional"))
    )
    (net (code "87") (name "Net-(U3-PE1_(TXD0))") (class "Default")
      (node (ref "J2") (pin "2") (pinfunction "2_2") (pintype "passive"))
      (node (ref "U3") (pin "3") (pinfunction "PE1_(TXD0)_3") (pintype "bidirectional"))
    )
    (net (code "88") (name "Net-(U3-PE3_(OC3A{slash}AIN1))") (class "Default")
      (node (ref "J2") (pin "6") (pinfunction "6_6") (pintype "passive"))
      (node (ref "U3") (pin "5") (pinfunction "PE3_(OC3A/AIN1)_5") (pintype "bidirectional"))
    )
    (net (code "89") (name "Net-(U3-PE4_(OC3B{slash}INT4))") (class "Default")
      (node (ref "J2") (pin "3") (pinfunction "3_3") (pintype "passive"))
      (node (ref "U3") (pin "6") (pinfunction "PE4_(OC3B/INT4)_6") (pintype "bidirectional"))
    )
    (net (code "90") (name "Net-(U3-PF0_(ADC0))") (class "Default")
      (node (ref "J5") (pin "1") (pinfunction "1_1") (pintype "passive"))
      (node (ref "U3") (pin "97") (pinfunction "PF0_(ADC0)_97") (pintype "bidirectional"))
    )
    (net (code "91") (name "Net-(U3-PF1_(ADC1))") (class "Default")
      (node (ref "J5") (pin "2") (pinfunction "2_2") (pintype "passive"))
      (node (ref "U3") (pin "96") (pinfunction "PF1_(ADC1)_96") (pintype "bidirectional"))
    )
    (net (code "92") (name "Net-(U3-PF2_(ADC2))") (class "Default")
      (node (ref "J5") (pin "3") (pinfunction "3_3") (pintype "passive"))
      (node (ref "U3") (pin "95") (pinfunction "PF2_(ADC2)_95") (pintype "bidirectional"))
    )
    (net (code "93") (name "Net-(U3-PF3_(ADC3))") (class "Default")
      (node (ref "J5") (pin "4") (pinfunction "4_4") (pintype "passive"))
      (node (ref "U3") (pin "94") (pinfunction "PF3_(ADC3)_94") (pintype "bidirectional"))
    )
    (net (code "94") (name "Net-(U3-PF4_(ADC4{slash}TCK))") (class "Default")
      (node (ref "J5") (pin "5") (pinfunction "5_5") (pintype "passive"))
      (node (ref "U3") (pin "93") (pinfunction "PF4_(ADC4/TCK)_93") (pintype "bidirectional"))
    )
    (net (code "95") (name "Net-(U3-PF5_(ADC5{slash}TMS))") (class "Default")
      (node (ref "J5") (pin "6") (pinfunction "6_6") (pintype "passive"))
      (node (ref "U3") (pin "92") (pinfunction "PF5_(ADC5/TMS)_92") (pintype "bidirectional"))
    )
    (net (code "96") (name "Net-(U3-PF6_(ADC6{slash}TDO))") (class "Default")
      (node (ref "J5") (pin "7") (pinfunction "7_7") (pintype "passive"))
      (node (ref "U3") (pin "91") (pinfunction "PF6_(ADC6/TDO)_91") (pintype "bidirectional"))
    )
    (net (code "97") (name "Net-(U3-PF7_(ADC7{slash}TDI))") (class "Default")
      (node (ref "J5") (pin "8") (pinfunction "8_8") (pintype "passive"))
      (node (ref "U3") (pin "90") (pinfunction "PF7_(ADC7/TDI)_90") (pintype "bidirectional"))
    )
    (net (code "98") (name "Net-(U3-XTAL1)") (class "Default")
      (node (ref "C10") (pin "1") (pinfunction "1_1") (pintype "passive"))
      (node (ref "R10") (pin "1") (pinfunction "1_1") (pintype "passive"))
      (node (ref "U3") (pin "34") (pinfunction "XTAL1_34") (pintype "input"))
      (node (ref "Y2") (pin "1") (pinfunction "1_1") (pintype "passive"))
    )
    (net (code "99") (name "Net-(U3-XTAL2)") (class "Default")
      (node (ref "C11") (pin "1") (pinfunction "1_1") (pintype "passive"))
      (node (ref "R10") (pin "2") (pinfunction "2_2") (pintype "passive"))
      (node (ref "U3") (pin "33") (pinfunction "XTAL2_33") (pintype "output"))
      (node (ref "Y2") (pin "2") (pinfunction "2_2") (pintype "passive"))
    )
    (net (code "100") (name "unconnected-(J4-Pad1)") (class "Default")
      (node (ref "J4") (pin "1") (pinfunction "1_1") (pintype "passive"))
    )
    (net (code "101") (name "unconnected-(KEY1-Pad5)") (class "Default")
      (node (ref "KEY1") (pin "5") (pinfunction "5_5") (pintype "passive"))
    )
    (net (code "102") (name "unconnected-(Micro USB1-ID-Pad4)") (class "Default")
      (node (ref "Micro USB1") (pin "4") (pinfunction "ID_4") (pintype "passive+no_connect"))
    )
    (net (code "103") (name "unconnected-(Micro USB1-MTN-Pad0)") (class "Default")
      (node (ref "Micro USB1") (pin "0") (pinfunction "MTN_0") (pintype "passive+no_connect"))
    )
    (net (code "104") (name "unconnected-(U2-CTS-Pad9)") (class "Default")
      (node (ref "U2") (pin "9") (pinfunction "CTS_9") (pintype "passive+no_connect"))
    )
    (net (code "105") (name "unconnected-(U2-DCD#-Pad12)") (class "Default")
      (node (ref "U2") (pin "12") (pinfunction "DCD#_12") (pintype "passive+no_connect"))
    )
    (net (code "106") (name "unconnected-(U2-DSR#-Pad10)") (class "Default")
      (node (ref "U2") (pin "10") (pinfunction "DSR#_10") (pintype "passive+no_connect"))
    )
    (net (code "107") (name "unconnected-(U2-R232-Pad15)") (class "Default")
      (node (ref "U2") (pin "15") (pinfunction "R232_15") (pintype "passive+no_connect"))
    )
    (net (code "108") (name "unconnected-(U2-RI#-Pad11)") (class "Default")
      (node (ref "U2") (pin "11") (pinfunction "RI#_11") (pintype "passive+no_connect"))
    )
    (net (code "109") (name "unconnected-(U2-RTS#-Pad14)") (class "Default")
      (node (ref "U2") (pin "14") (pinfunction "RTS#_14") (pintype "passive+no_connect"))
    )
    (net (code "110") (name "unconnected-(U3-PD4_(ICP1)-Pad47)") (class "Default")
      (node (ref "U3") (pin "47") (pinfunction "PD4_(ICP1)_47") (pintype "bidirectional+no_connect"))
    )
    (net (code "111") (name "unconnected-(U3-PD5_(XCK1)-Pad48)") (class "Default")
      (node (ref "U3") (pin "48") (pinfunction "PD5_(XCK1)_48") (pintype "bidirectional+no_connect"))
    )
    (net (code "112") (name "unconnected-(U3-PD6_(T1)-Pad49)") (class "Default")
      (node (ref "U3") (pin "49") (pinfunction "PD6_(T1)_49") (pintype "bidirectional+no_connect"))
    )
    (net (code "113") (name "unconnected-(U3-PE2_(XCK0{slash}AIN0)-Pad4)") (class "Default")
      (node (ref "U3") (pin "4") (pinfunction "PE2_(XCK0/AIN0)_4") (pintype "bidirectional+no_connect"))
    )
    (net (code "114") (name "unconnected-(U3-PE6_(T3{slash}INT6)-Pad8)") (class "Default")
      (node (ref "U3") (pin "8") (pinfunction "PE6_(T3/INT6)_8") (pintype "bidirectional+no_connect"))
    )
    (net (code "115") (name "unconnected-(U3-PE7_(CLKO{slash}ICP3{slash}INT7)-Pad9)") (class "Default")
      (node (ref "U3") (pin "9") (pinfunction "PE7_(CLKO/ICP3/INT7)_9") (pintype "bidirectional+no_connect"))
    )
    (net (code "116") (name "unconnected-(U3-PG3_(TOSC2)-Pad28)") (class "Default")
      (node (ref "U3") (pin "28") (pinfunction "PG3_(TOSC2)_28") (pintype "bidirectional+no_connect"))
    )
    (net (code "117") (name "unconnected-(U3-PG4_(TOSC1)-Pad29)") (class "Default")
      (node (ref "U3") (pin "29") (pinfunction "PG4_(TOSC1)_29") (pintype "bidirectional+no_connect"))
    )
    (net (code "118") (name "unconnected-(U3-PH2_(XCK2)-Pad14)") (class "Default")
      (node (ref "U3") (pin "14") (pinfunction "PH2_(XCK2)_14") (pintype "bidirectional+no_connect"))
    )
    (net (code "119") (name "unconnected-(U3-PH7_(T4)-Pad27)") (class "Default")
      (node (ref "U3") (pin "27") (pinfunction "PH7_(T4)_27") (pintype "bidirectional+no_connect"))
    )
    (net (code "120") (name "unconnected-(U3-PJ2_(XCK3{slash}PCINT11)-Pad65)") (class "Default")
      (node (ref "U3") (pin "65") (pinfunction "PJ2_(XCK3/PCINT11)_65") (pintype "bidirectional+no_connect"))
    )
    (net (code "121") (name "unconnected-(U3-PJ3_(PCINT12)-Pad66)") (class "Default")
      (node (ref "U3") (pin "66") (pinfunction "PJ3_(PCINT12)_66") (pintype "bidirectional+no_connect"))
    )
    (net (code "122") (name "unconnected-(U3-PJ4_(PCINT13)-Pad67)") (class "Default")
      (node (ref "U3") (pin "67") (pinfunction "PJ4_(PCINT13)_67") (pintype "bidirectional+no_connect"))
    )
    (net (code "123") (name "unconnected-(U3-PJ5_(PCINT14)-Pad68)") (class "Default")
      (node (ref "U3") (pin "68") (pinfunction "PJ5_(PCINT14)_68") (pintype "bidirectional+no_connect"))
    )
    (net (code "124") (name "unconnected-(U3-PJ6_(PCINT15)-Pad69)") (class "Default")
      (node (ref "U3") (pin "69") (pinfunction "PJ6_(PCINT15)_69") (pintype "bidirectional+no_connect"))
    )
    (net (code "125") (name "unconnected-(U3-PJ7-Pad79)") (class "Default")
      (node (ref "U3") (pin "79") (pinfunction "PJ7_79") (pintype "bidirectional+no_connect"))
    )
    (net (code "126") (name "unconnected-(U3-VCC-Pad10)") (class "Default")
      (node (ref "U3") (pin "10") (pinfunction "VCC_10") (pintype "power_in"))
    )
    (net (code "127") (name "unconnected-(U3-VCC-Pad31)") (class "Default")
      (node (ref "U3") (pin "31") (pinfunction "VCC_31") (pintype "power_in"))
    )
    (net (code "128") (name "unconnected-(U3-VCC-Pad61)") (class "Default")
      (node (ref "U3") (pin "61") (pinfunction "VCC_61") (pintype "power_in"))
    )
    (net (code "129") (name "unconnected-(U3-VCC-Pad80)") (class "Default")
      (node (ref "U3") (pin "80") (pinfunction "VCC_80") (pintype "power_in"))
    )
  )
)
